# enginneeee.net
KiCad netlist of a schematic drawn in EasyEDA Pro
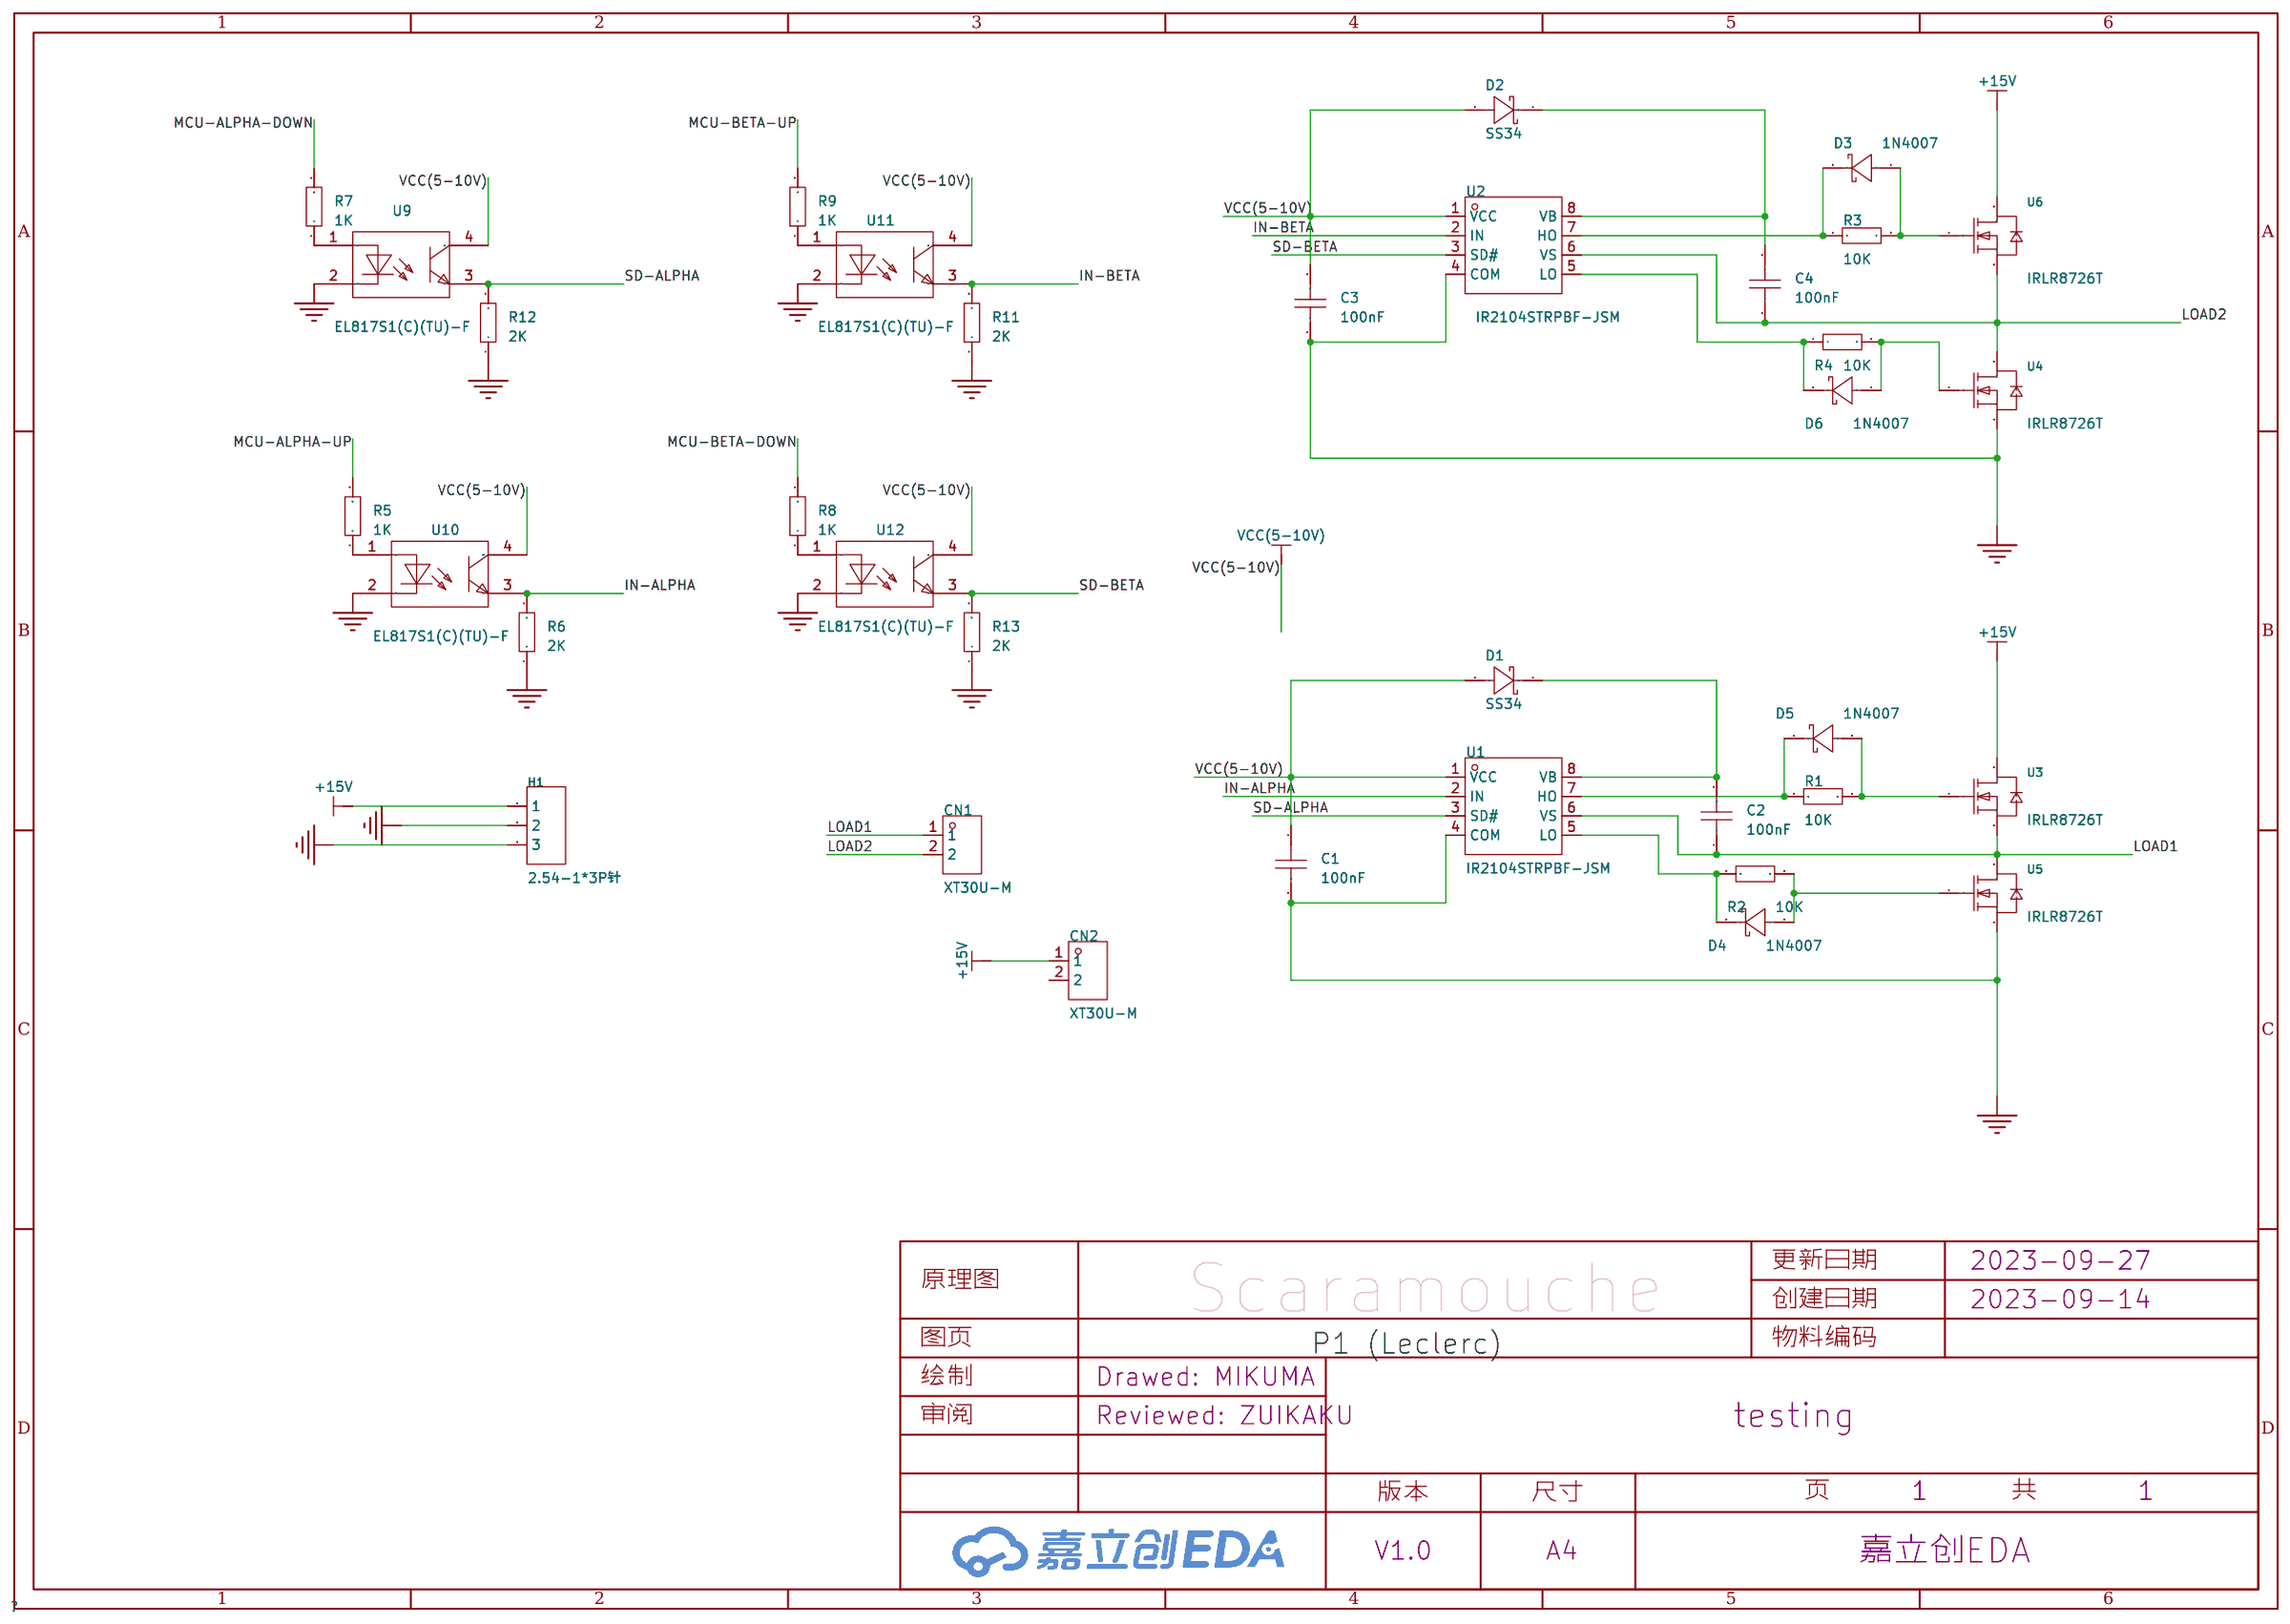
[diagram p0: schematic sheet]

(export (version "E")
  (design (tool "Eeschema 10.0.6"))
  (components
    (comp (ref "C1")
      (value "100nF")
      (footprint "easyedapro:C0603")
      (libsource (lib "easyedapro") (part "CapAcitance"))
    )
    (comp (ref "C2")
      (value "100nF")
      (footprint "easyedapro:C0603")
      (libsource (lib "easyedapro") (part "CapAcitance"))
    )
    (comp (ref "C3")
      (value "100nF")
      (footprint "easyedapro:C0603")
      (libsource (lib "easyedapro") (part "CapAcitance"))
    )
    (comp (ref "C4")
      (value "100nF")
      (footprint "easyedapro:C0603")
      (libsource (lib "easyedapro") (part "CapAcitance"))
    )
    (comp (ref "CN1")
      (value "XT30U-M")
      (footprint "easyedapro:CONN-TH_XT30U-M")
      (description "模型插头轻量版锂电池插头")
      (fields (field (name "Manufacturer") "AMASS(艾迈斯)"))
      (libsource (lib "easyedapro") (part "XT30U-M"))
    )
    (comp (ref "CN2")
      (value "XT30U-M")
      (footprint "easyedapro:CONN-TH_XT30U-M")
      (description "模型插头轻量版锂电池插头")
      (fields (field (name "Manufacturer") "AMASS(艾迈斯)"))
      (libsource (lib "easyedapro") (part "XT30U-M"))
    )
    (comp (ref "D1")
      (value "SS34")
      (footprint "easyedapro:SMA_L4.3-W2.5-LS5.0-RD")
      (description "二极管配置:独立式;直流反向耐压(Vr):40V;平均整流电流(Io):3A;正向压降(Vf):550mV@3A;")
      (fields (field (name "Manufacturer") "TWGMC(台湾迪嘉)"))
      (libsource (lib "easyedapro") (part "SS34_C727060"))
    )
    (comp (ref "D2")
      (value "SS34")
      (footprint "easyedapro:SMA_L4.3-W2.5-LS5.0-RD")
      (description "二极管配置:独立式;直流反向耐压(Vr):40V;平均整流电流(Io):3A;正向压降(Vf):550mV@3A;")
      (fields (field (name "Manufacturer") "TWGMC(台湾迪嘉)"))
      (libsource (lib "easyedapro") (part "SS34_C727060"))
    )
    (comp (ref "D3")
      (value "1N4007")
      (footprint "easyedapro:SMA_L4.3-W2.6-LS5.1-R-RD")
      (description "二极管配置:-;直流反向耐压(Vr):1kV;平均整流电流(Io):1A;正向压降(Vf):1.1V@1A;反向电流(Ir):5uA@1kV;")
      (fields (field (name "Manufacturer") "YONGYUTAI(永裕泰)"))
      (libsource (lib "easyedapro") (part "1N4007_C2892673"))
    )
    (comp (ref "D4")
      (value "1N4007")
      (footprint "easyedapro:SMA_L4.3-W2.6-LS5.1-R-RD")
      (description "二极管配置:-;直流反向耐压(Vr):1kV;平均整流电流(Io):1A;正向压降(Vf):1.1V@1A;反向电流(Ir):5uA@1kV;")
      (fields (field (name "Manufacturer") "YONGYUTAI(永裕泰)"))
      (libsource (lib "easyedapro") (part "1N4007_C2892673"))
    )
    (comp (ref "D5")
      (value "1N4007")
      (footprint "easyedapro:SMA_L4.3-W2.6-LS5.1-R-RD")
      (description "二极管配置:-;直流反向耐压(Vr):1kV;平均整流电流(Io):1A;正向压降(Vf):1.1V@1A;反向电流(Ir):5uA@1kV;")
      (fields (field (name "Manufacturer") "YONGYUTAI(永裕泰)"))
      (libsource (lib "easyedapro") (part "1N4007_C2892673"))
    )
    (comp (ref "D6")
      (value "1N4007")
      (footprint "easyedapro:SMA_L4.3-W2.6-LS5.1-R-RD")
      (description "二极管配置:-;直流反向耐压(Vr):1kV;平均整流电流(Io):1A;正向压降(Vf):1.1V@1A;反向电流(Ir):5uA@1kV;")
      (fields (field (name "Manufacturer") "YONGYUTAI(永裕泰)"))
      (libsource (lib "easyedapro") (part "1N4007_C2892673"))
    )
    (comp (ref "H1")
      (value "2.54-1*3P针")
      (footprint "easyedapro:HDR-TH_3P-P2.54-V-M-1")
      (fields (field (name "Manufacturer") "BOOMELE(博穆精密)"))
      (libsource (lib "easyedapro") (part "Header-Male-2.54_1x3"))
    )
    (comp (ref "R1") (value "10K") (footprint "easyedapro:R0603") (libsource (lib "easyedapro") (part "电阻")))
    (comp (ref "R2") (value "10K") (footprint "easyedapro:R0603") (libsource (lib "easyedapro") (part "电阻")))
    (comp (ref "R3") (value "10K") (footprint "easyedapro:R0603") (libsource (lib "easyedapro") (part "电阻")))
    (comp (ref "R4") (value "10K") (footprint "easyedapro:R0603") (libsource (lib "easyedapro") (part "电阻")))
    (comp (ref "R5") (value "1K") (footprint "easyedapro:R0603") (libsource (lib "easyedapro") (part "电阻")))
    (comp (ref "R6") (value "2K") (footprint "easyedapro:R0603") (libsource (lib "easyedapro") (part "电阻")))
    (comp (ref "R7") (value "1K") (footprint "easyedapro:R0603") (libsource (lib "easyedapro") (part "电阻")))
    (comp (ref "R8") (value "1K") (footprint "easyedapro:R0603") (libsource (lib "easyedapro") (part "电阻")))
    (comp (ref "R9") (value "1K") (footprint "easyedapro:R0603") (libsource (lib "easyedapro") (part "电阻")))
    (comp (ref "R11") (value "2K") (footprint "easyedapro:R0603") (libsource (lib "easyedapro") (part "电阻")))
    (comp (ref "R12") (value "2K") (footprint "easyedapro:R0603") (libsource (lib "easyedapro") (part "电阻")))
    (comp (ref "R13") (value "2K") (footprint "easyedapro:R0603") (libsource (lib "easyedapro") (part "电阻")))
    (comp (ref "U1")
      (value "IR2104STRPBF-JSM")
      (footprint "easyedapro:SOIC-8_L4.9-W3.9-P1.27-LS6.0-BL")
      (fields (field (name "Manufacturer") "JSMSEMI(杰盛微)"))
      (libsource (lib "easyedapro") (part "IR2104STR"))
    )
    (comp (ref "U2")
      (value "IR2104STRPBF-JSM")
      (footprint "easyedapro:SOIC-8_L4.9-W3.9-P1.27-LS6.0-BL")
      (fields (field (name "Manufacturer") "JSMSEMI(杰盛微)"))
      (libsource (lib "easyedapro") (part "IR2104STR"))
    )
    (comp (ref "U3")
      (value "IRLR8726T")
      (footprint "easyedapro:TO-252-3_L6.5-W5.8-P4.60-LS9.9-BR")
      (description "类型:N沟道;漏源电压(Vdss):30V;连续漏极电流(Id):80A;功率(Pd):54W;导通电阻(RDS(on)@Vgs,Id):6mΩ@10V;")
      (fields (field (name "Manufacturer") "HXY MOSFET(华轩阳电子)"))
      (libsource (lib "easyedapro") (part "IRLR8726T"))
    )
    (comp (ref "U4")
      (value "IRLR8726T")
      (footprint "easyedapro:TO-252-3_L6.5-W5.8-P4.60-LS9.9-BR")
      (description "类型:N沟道;漏源电压(Vdss):30V;连续漏极电流(Id):80A;功率(Pd):54W;导通电阻(RDS(on)@Vgs,Id):6mΩ@10V;")
      (fields (field (name "Manufacturer") "HXY MOSFET(华轩阳电子)"))
      (libsource (lib "easyedapro") (part "IRLR8726T"))
    )
    (comp (ref "U5")
      (value "IRLR8726T")
      (footprint "easyedapro:TO-252-3_L6.5-W5.8-P4.60-LS9.9-BR")
      (description "类型:N沟道;漏源电压(Vdss):30V;连续漏极电流(Id):80A;功率(Pd):54W;导通电阻(RDS(on)@Vgs,Id):6mΩ@10V;")
      (fields (field (name "Manufacturer") "HXY MOSFET(华轩阳电子)"))
      (libsource (lib "easyedapro") (part "IRLR8726T"))
    )
    (comp (ref "U6")
      (value "IRLR8726T")
      (footprint "easyedapro:TO-252-3_L6.5-W5.8-P4.60-LS9.9-BR")
      (description "类型:N沟道;漏源电压(Vdss):30V;连续漏极电流(Id):80A;功率(Pd):54W;导通电阻(RDS(on)@Vgs,Id):6mΩ@10V;")
      (fields (field (name "Manufacturer") "HXY MOSFET(华轩阳电子)"))
      (libsource (lib "easyedapro") (part "IRLR8726T"))
    )
    (comp (ref "U9")
      (value "EL817S1(C)(TU)-F")
      (footprint "easyedapro:OPTO-SMD-4_L4.6-W6.5-P2.54-LS10.3-TL")
      (fields (field (name "Manufacturer") "EVERLIGHT(亿光)"))
      (libsource (lib "easyedapro") (part "EL817S1(C)(TU)-F"))
    )
    (comp (ref "U10")
      (value "EL817S1(C)(TU)-F")
      (footprint "easyedapro:OPTO-SMD-4_L4.6-W6.5-P2.54-LS10.3-TL")
      (fields (field (name "Manufacturer") "EVERLIGHT(亿光)"))
      (libsource (lib "easyedapro") (part "EL817S1(C)(TU)-F"))
    )
    (comp (ref "U11")
      (value "EL817S1(C)(TU)-F")
      (footprint "easyedapro:OPTO-SMD-4_L4.6-W6.5-P2.54-LS10.3-TL")
      (fields (field (name "Manufacturer") "EVERLIGHT(亿光)"))
      (libsource (lib "easyedapro") (part "EL817S1(C)(TU)-F"))
    )
    (comp (ref "U12")
      (value "EL817S1(C)(TU)-F")
      (footprint "easyedapro:OPTO-SMD-4_L4.6-W6.5-P2.54-LS10.3-TL")
      (fields (field (name "Manufacturer") "EVERLIGHT(亿光)"))
      (libsource (lib "easyedapro") (part "EL817S1(C)(TU)-F"))
    )
  )
  (nets
    (net (code "1") (name "+15V") (class "Default")
      (node (ref "CN2") (pin "1") (pinfunction "1_1") (pintype "input"))
      (node (ref "H1") (pin "1") (pinfunction "1_1") (pintype "input"))
      (node (ref "U3") (pin "2") (pinfunction "D_2") (pintype "input"))
      (node (ref "U6") (pin "2") (pinfunction "D_2") (pintype "input"))
    )
    (net (code "2") (name "/IN-ALPHA") (class "Default")
      (node (ref "R6") (pin "2") (pinfunction "2_2") (pintype "input"))
      (node (ref "U1") (pin "2") (pinfunction "IN_2") (pintype "input"))
      (node (ref "U10") (pin "3") (pinfunction "EM_3") (pintype "input"))
    )
    (net (code "3") (name "/IN-BETA") (class "Default")
      (node (ref "R11") (pin "2") (pinfunction "2_2") (pintype "input"))
      (node (ref "U11") (pin "3") (pinfunction "EM_3") (pintype "input"))
      (node (ref "U2") (pin "2") (pinfunction "IN_2") (pintype "input"))
    )
    (net (code "4") (name "/LOAD1") (class "Default")
      (node (ref "C2") (pin "1") (pinfunction "1_1") (pintype "input"))
      (node (ref "CN1") (pin "1") (pinfunction "1_1") (pintype "input"))
      (node (ref "U1") (pin "6") (pinfunction "VS_6") (pintype "input"))
      (node (ref "U3") (pin "3") (pinfunction "S_3") (pintype "input"))
      (node (ref "U5") (pin "2") (pinfunction "D_2") (pintype "input"))
    )
    (net (code "5") (name "/LOAD2") (class "Default")
      (node (ref "C4") (pin "1") (pinfunction "1_1") (pintype "input"))
      (node (ref "CN1") (pin "2") (pinfunction "2_2") (pintype "input"))
      (node (ref "U2") (pin "6") (pinfunction "VS_6") (pintype "input"))
      (node (ref "U4") (pin "2") (pinfunction "D_2") (pintype "input"))
      (node (ref "U6") (pin "3") (pinfunction "S_3") (pintype "input"))
    )
    (net (code "6") (name "/MCU-ALPHA-DOWN") (class "Default")
      (node (ref "R7") (pin "2") (pinfunction "2_2") (pintype "input"))
    )
    (net (code "7") (name "/MCU-ALPHA-UP") (class "Default")
      (node (ref "R5") (pin "2") (pinfunction "2_2") (pintype "input"))
    )
    (net (code "8") (name "/MCU-BETA-DOWN") (class "Default")
      (node (ref "R8") (pin "2") (pinfunction "2_2") (pintype "input"))
    )
    (net (code "9") (name "/MCU-BETA-UP") (class "Default")
      (node (ref "R9") (pin "2") (pinfunction "2_2") (pintype "input"))
    )
    (net (code "10") (name "/SD-ALPHA") (class "Default")
      (node (ref "R12") (pin "2") (pinfunction "2_2") (pintype "input"))
      (node (ref "U1") (pin "3") (pinfunction "SD#_3") (pintype "input"))
      (node (ref "U9") (pin "3") (pinfunction "EM_3") (pintype "input"))
    )
    (net (code "11") (name "/SD-BETA") (class "Default")
      (node (ref "R13") (pin "2") (pinfunction "2_2") (pintype "input"))
      (node (ref "U12") (pin "3") (pinfunction "EM_3") (pintype "input"))
      (node (ref "U2") (pin "3") (pinfunction "SD#_3") (pintype "input"))
    )
    (net (code "12") (name "GND") (class "Default")
      (node (ref "C1") (pin "2") (pinfunction "2_2") (pintype "input"))
      (node (ref "C3") (pin "1") (pinfunction "1_1") (pintype "input"))
      (node (ref "H1") (pin "2") (pinfunction "2_2") (pintype "input"))
      (node (ref "R11") (pin "1") (pinfunction "1_1") (pintype "input"))
      (node (ref "R12") (pin "1") (pinfunction "1_1") (pintype "input"))
      (node (ref "R13") (pin "1") (pinfunction "1_1") (pintype "input"))
      (node (ref "R6") (pin "1") (pinfunction "1_1") (pintype "input"))
      (node (ref "U1") (pin "4") (pinfunction "COM_4") (pintype "input"))
      (node (ref "U2") (pin "4") (pinfunction "COM_4") (pintype "input"))
      (node (ref "U4") (pin "3") (pinfunction "S_3") (pintype "input"))
      (node (ref "U5") (pin "3") (pinfunction "S_3") (pintype "input"))
    )
    (net (code "13") (name "GND1") (class "Default")
      (node (ref "H1") (pin "3") (pinfunction "3_3") (pintype "input"))
      (node (ref "U10") (pin "2") (pinfunction "CAT_2") (pintype "input"))
      (node (ref "U11") (pin "2") (pinfunction "CAT_2") (pintype "input"))
      (node (ref "U12") (pin "2") (pinfunction "CAT_2") (pintype "input"))
      (node (ref "U9") (pin "2") (pinfunction "CAT_2") (pintype "input"))
    )
    (net (code "14") (name "Net-(D1-C)") (class "Default")
      (node (ref "C2") (pin "2") (pinfunction "2_2") (pintype "input"))
      (node (ref "D1") (pin "1") (pinfunction "C_1") (pintype "input"))
      (node (ref "U1") (pin "8") (pinfunction "VB_8") (pintype "input"))
    )
    (net (code "15") (name "Net-(D2-C)") (class "Default")
      (node (ref "C4") (pin "2") (pinfunction "2_2") (pintype "input"))
      (node (ref "D2") (pin "1") (pinfunction "C_1") (pintype "input"))
      (node (ref "U2") (pin "8") (pinfunction "VB_8") (pintype "input"))
    )
    (net (code "16") (name "Net-(D3-A)") (class "Default")
      (node (ref "D3") (pin "1") (pinfunction "A_1") (pintype "input"))
      (node (ref "R3") (pin "2") (pinfunction "2_2") (pintype "input"))
      (node (ref "U6") (pin "1") (pinfunction "G_1") (pintype "input"))
    )
    (net (code "17") (name "Net-(D3-K)") (class "Default")
      (node (ref "D3") (pin "2") (pinfunction "K_2") (pintype "input"))
      (node (ref "R3") (pin "1") (pinfunction "1_1") (pintype "input"))
      (node (ref "U2") (pin "7") (pinfunction "HO_7") (pintype "input"))
    )
    (net (code "18") (name "Net-(D4-A)") (class "Default")
      (node (ref "D4") (pin "1") (pinfunction "A_1") (pintype "input"))
      (node (ref "R2") (pin "2") (pinfunction "2_2") (pintype "input"))
      (node (ref "U5") (pin "1") (pinfunction "G_1") (pintype "input"))
    )
    (net (code "19") (name "Net-(D4-K)") (class "Default")
      (node (ref "D4") (pin "2") (pinfunction "K_2") (pintype "input"))
      (node (ref "R2") (pin "1") (pinfunction "1_1") (pintype "input"))
      (node (ref "U1") (pin "5") (pinfunction "LO_5") (pintype "input"))
    )
    (net (code "20") (name "Net-(D5-A)") (class "Default")
      (node (ref "D5") (pin "1") (pinfunction "A_1") (pintype "input"))
      (node (ref "R1") (pin "2") (pinfunction "2_2") (pintype "input"))
      (node (ref "U3") (pin "1") (pinfunction "G_1") (pintype "input"))
    )
    (net (code "21") (name "Net-(D5-K)") (class "Default")
      (node (ref "D5") (pin "2") (pinfunction "K_2") (pintype "input"))
      (node (ref "R1") (pin "1") (pinfunction "1_1") (pintype "input"))
      (node (ref "U1") (pin "7") (pinfunction "HO_7") (pintype "input"))
    )
    (net (code "22") (name "Net-(D6-A)") (class "Default")
      (node (ref "D6") (pin "1") (pinfunction "A_1") (pintype "input"))
      (node (ref "R4") (pin "2") (pinfunction "2_2") (pintype "input"))
      (node (ref "U4") (pin "1") (pinfunction "G_1") (pintype "input"))
    )
    (net (code "23") (name "Net-(D6-K)") (class "Default")
      (node (ref "D6") (pin "2") (pinfunction "K_2") (pintype "input"))
      (node (ref "R4") (pin "1") (pinfunction "1_1") (pintype "input"))
      (node (ref "U2") (pin "5") (pinfunction "LO_5") (pintype "input"))
    )
    (net (code "24") (name "Net-(U9-AN)") (class "Default")
      (node (ref "R7") (pin "1") (pinfunction "1_1") (pintype "input"))
      (node (ref "U9") (pin "1") (pinfunction "AN_1") (pintype "input"))
    )
    (net (code "25") (name "Net-(U10-AN)") (class "Default")
      (node (ref "R5") (pin "1") (pinfunction "1_1") (pintype "input"))
      (node (ref "U10") (pin "1") (pinfunction "AN_1") (pintype "input"))
    )
    (net (code "26") (name "Net-(U11-AN)") (class "Default")
      (node (ref "R9") (pin "1") (pinfunction "1_1") (pintype "input"))
      (node (ref "U11") (pin "1") (pinfunction "AN_1") (pintype "input"))
    )
    (net (code "27") (name "Net-(U12-AN)") (class "Default")
      (node (ref "R8") (pin "1") (pinfunction "1_1") (pintype "input"))
      (node (ref "U12") (pin "1") (pinfunction "AN_1") (pintype "input"))
    )
    (net (code "28") (name "VCC(5-10V)") (class "Default")
      (node (ref "C1") (pin "1") (pinfunction "1_1") (pintype "input"))
      (node (ref "C3") (pin "2") (pinfunction "2_2") (pintype "input"))
      (node (ref "D1") (pin "2") (pinfunction "A_2") (pintype "input"))
      (node (ref "D2") (pin "2") (pinfunction "A_2") (pintype "input"))
      (node (ref "U1") (pin "1") (pinfunction "VCC_1") (pintype "input"))
      (node (ref "U10") (pin "4") (pinfunction "COL_4") (pintype "input"))
      (node (ref "U11") (pin "4") (pinfunction "COL_4") (pintype "input"))
      (node (ref "U12") (pin "4") (pinfunction "COL_4") (pintype "input"))
      (node (ref "U2") (pin "1") (pinfunction "VCC_1") (pintype "input"))
      (node (ref "U9") (pin "4") (pinfunction "COL_4") (pintype "input"))
    )
    (net (code "29") (name "unconnected-(CN2-Pad2)") (class "Default")
      (node (ref "CN2") (pin "2") (pinfunction "2_2") (pintype "input"))
    )
  )
)
